# LWIR_FPGA_CSI.net
KiCad netlist of a schematic drawn in Altium Designer
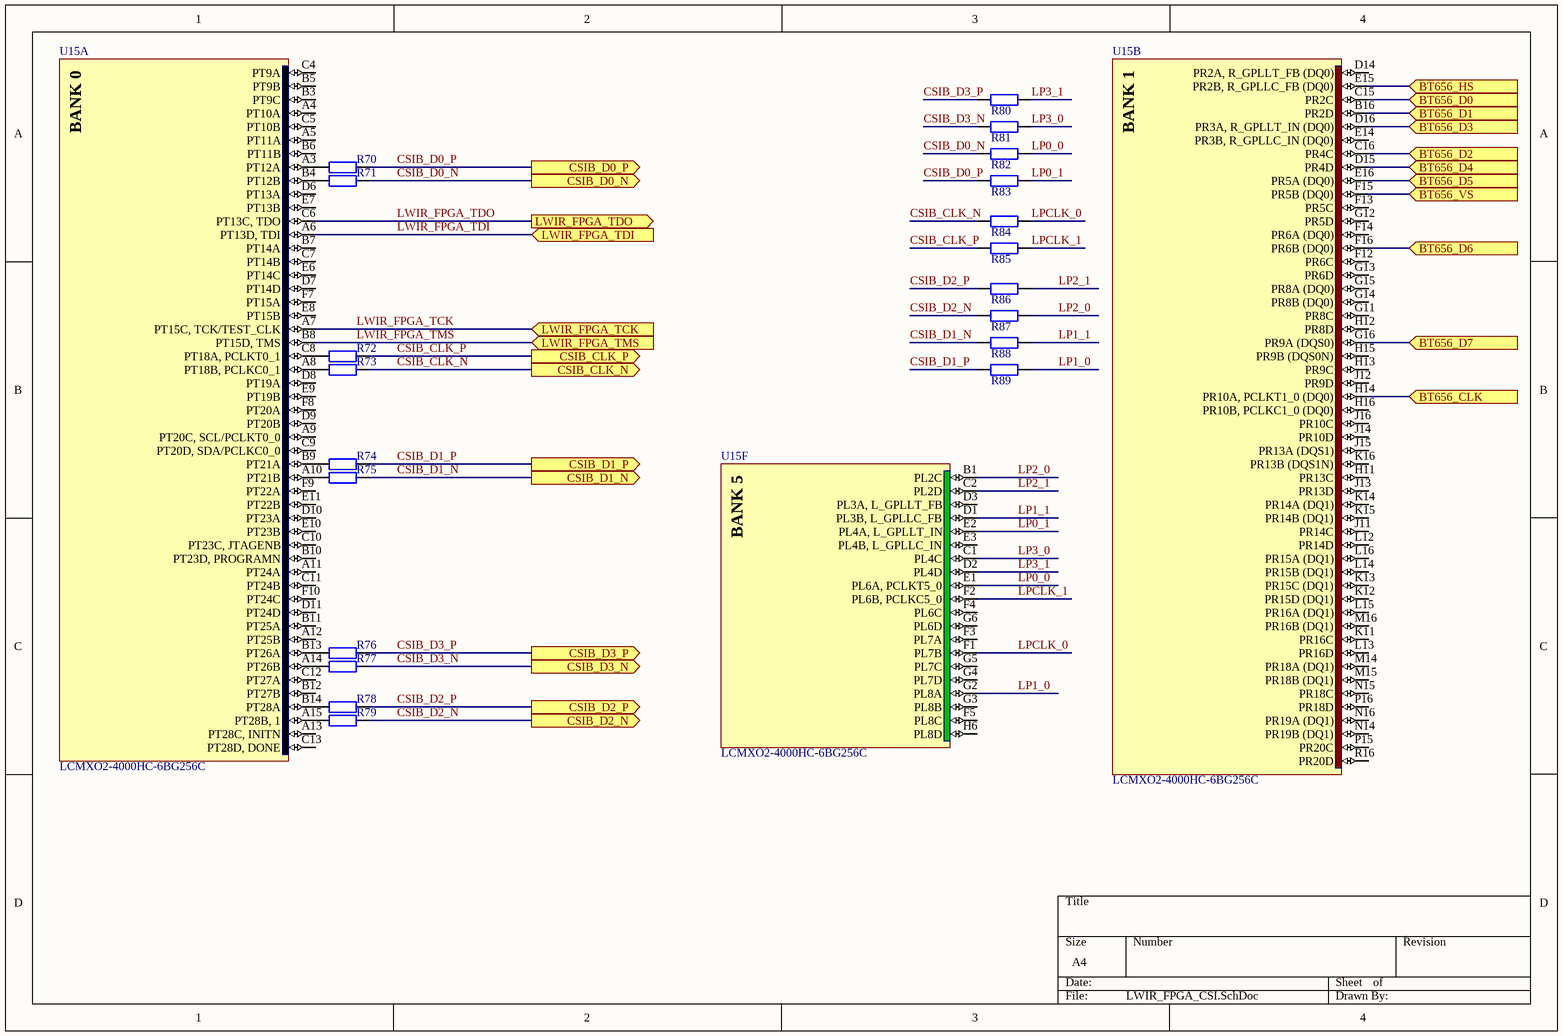
[diagram p0: LWIR_FPGA_CSI.SchDoc]

(export (version "E")
  (design (tool "Eeschema 10.0.6"))
  (components
    (comp (ref "R70")
      (value "CRCW0402330RFKED")
      (footprint "0402R_M")
      (description "RES SMD 330 OHM 1% 1/16W 0402")
      (fields (field (name "MANUFACTURER") "Vishay Dale") (field (name "TOLERANCE") "±1%"))
      (libsource (lib "KMTI-main") (part "CRCW0402330RFKED"))
    )
    (comp (ref "R71")
      (value "CRCW0402330RFKED")
      (footprint "0402R_M")
      (description "RES SMD 330 OHM 1% 1/16W 0402")
      (fields (field (name "MANUFACTURER") "Vishay Dale") (field (name "TOLERANCE") "±1%"))
      (libsource (lib "KMTI-main") (part "CRCW0402330RFKED"))
    )
    (comp (ref "R72")
      (value "CRCW0402330RFKED")
      (footprint "0402R_M")
      (description "RES SMD 330 OHM 1% 1/16W 0402")
      (fields (field (name "MANUFACTURER") "Vishay Dale") (field (name "TOLERANCE") "±1%"))
      (libsource (lib "KMTI-main") (part "CRCW0402330RFKED"))
    )
    (comp (ref "R73")
      (value "CRCW0402330RFKED")
      (footprint "0402R_M")
      (description "RES SMD 330 OHM 1% 1/16W 0402")
      (fields (field (name "MANUFACTURER") "Vishay Dale") (field (name "TOLERANCE") "±1%"))
      (libsource (lib "KMTI-main") (part "CRCW0402330RFKED"))
    )
    (comp (ref "R74")
      (value "CRCW0402330RFKED")
      (footprint "0402R_M")
      (description "RES SMD 330 OHM 1% 1/16W 0402")
      (fields (field (name "MANUFACTURER") "Vishay Dale") (field (name "TOLERANCE") "±1%"))
      (libsource (lib "KMTI-main") (part "CRCW0402330RFKED"))
    )
    (comp (ref "R75")
      (value "CRCW0402330RFKED")
      (footprint "0402R_M")
      (description "RES SMD 330 OHM 1% 1/16W 0402")
      (fields (field (name "MANUFACTURER") "Vishay Dale") (field (name "TOLERANCE") "±1%"))
      (libsource (lib "KMTI-main") (part "CRCW0402330RFKED"))
    )
    (comp (ref "R76")
      (value "CRCW0402330RFKED")
      (footprint "0402R_M")
      (description "RES SMD 330 OHM 1% 1/16W 0402")
      (fields (field (name "MANUFACTURER") "Vishay Dale") (field (name "TOLERANCE") "±1%"))
      (libsource (lib "KMTI-main") (part "CRCW0402330RFKED"))
    )
    (comp (ref "R77")
      (value "CRCW0402330RFKED")
      (footprint "0402R_M")
      (description "RES SMD 330 OHM 1% 1/16W 0402")
      (fields (field (name "MANUFACTURER") "Vishay Dale") (field (name "TOLERANCE") "±1%"))
      (libsource (lib "KMTI-main") (part "CRCW0402330RFKED"))
    )
    (comp (ref "R78")
      (value "CRCW0402330RFKED")
      (footprint "0402R_M")
      (description "RES SMD 330 OHM 1% 1/16W 0402")
      (fields (field (name "MANUFACTURER") "Vishay Dale") (field (name "TOLERANCE") "±1%"))
      (libsource (lib "KMTI-main") (part "CRCW0402330RFKED"))
    )
    (comp (ref "R79")
      (value "CRCW0402330RFKED")
      (footprint "0402R_M")
      (description "RES SMD 330 OHM 1% 1/16W 0402")
      (fields (field (name "MANUFACTURER") "Vishay Dale") (field (name "TOLERANCE") "±1%"))
      (libsource (lib "KMTI-main") (part "CRCW0402330RFKED"))
    )
    (comp (ref "R80")
      (value "CRCW040249R9FKED")
      (footprint "0402R_M")
      (description "RES SMD 49.9 OHM 1% 1/16W 0402")
      (fields (field (name "MANUFACTURER") "Vishay Dale") (field (name "TOLERANCE") "±1%"))
      (libsource (lib "KMTI-main") (part "CRCW040249R9FKED"))
    )
    (comp (ref "R81")
      (value "CRCW040249R9FKED")
      (footprint "0402R_M")
      (description "RES SMD 49.9 OHM 1% 1/16W 0402")
      (fields (field (name "MANUFACTURER") "Vishay Dale") (field (name "TOLERANCE") "±1%"))
      (libsource (lib "KMTI-main") (part "CRCW040249R9FKED"))
    )
    (comp (ref "R82")
      (value "CRCW040249R9FKED")
      (footprint "0402R_M")
      (description "RES SMD 49.9 OHM 1% 1/16W 0402")
      (fields (field (name "MANUFACTURER") "Vishay Dale") (field (name "TOLERANCE") "±1%"))
      (libsource (lib "KMTI-main") (part "CRCW040249R9FKED"))
    )
    (comp (ref "R83")
      (value "CRCW040249R9FKED")
      (footprint "0402R_M")
      (description "RES SMD 49.9 OHM 1% 1/16W 0402")
      (fields (field (name "MANUFACTURER") "Vishay Dale") (field (name "TOLERANCE") "±1%"))
      (libsource (lib "KMTI-main") (part "CRCW040249R9FKED"))
    )
    (comp (ref "R84")
      (value "CRCW040249R9FKED")
      (footprint "0402R_M")
      (description "RES SMD 49.9 OHM 1% 1/16W 0402")
      (fields (field (name "MANUFACTURER") "Vishay Dale") (field (name "TOLERANCE") "±1%"))
      (libsource (lib "KMTI-main") (part "CRCW040249R9FKED"))
    )
    (comp (ref "R85")
      (value "CRCW040249R9FKED")
      (footprint "0402R_M")
      (description "RES SMD 49.9 OHM 1% 1/16W 0402")
      (fields (field (name "MANUFACTURER") "Vishay Dale") (field (name "TOLERANCE") "±1%"))
      (libsource (lib "KMTI-main") (part "CRCW040249R9FKED"))
    )
    (comp (ref "R86")
      (value "CRCW040249R9FKED")
      (footprint "0402R_M")
      (description "RES SMD 49.9 OHM 1% 1/16W 0402")
      (fields (field (name "MANUFACTURER") "Vishay Dale") (field (name "TOLERANCE") "±1%"))
      (libsource (lib "") (part "CRCW040249R9FKED_1"))
    )
    (comp (ref "R87")
      (value "CRCW040249R9FKED")
      (footprint "0402R_M")
      (description "RES SMD 49.9 OHM 1% 1/16W 0402")
      (fields (field (name "MANUFACTURER") "Vishay Dale") (field (name "TOLERANCE") "±1%"))
      (libsource (lib "") (part "CRCW040249R9FKED_1"))
    )
    (comp (ref "R88")
      (value "CRCW040249R9FKED")
      (footprint "0402R_M")
      (description "RES SMD 49.9 OHM 1% 1/16W 0402")
      (fields (field (name "MANUFACTURER") "Vishay Dale") (field (name "TOLERANCE") "±1%"))
      (libsource (lib "") (part "CRCW040249R9FKED_1"))
    )
    (comp (ref "R89")
      (value "CRCW040249R9FKED")
      (footprint "0402R_M")
      (description "RES SMD 49.9 OHM 1% 1/16W 0402")
      (fields (field (name "MANUFACTURER") "Vishay Dale") (field (name "TOLERANCE") "±1%"))
      (libsource (lib "") (part "CRCW040249R9FKED_1"))
    )
    (comp (ref "U15")
      (value "LCMXO2-4000HC-6BG256C")
      (footprint "caBGA256")
      (libsource (lib "Altium Content Vault") (part "PLD-LTMXO2-4000-GA256"))
    )
  )
  (nets
    (net (code "1") (name "/BT656_CLK") (class "Default")
      (node (ref "U15") (pin "H14") (pinfunction "PR10A,_PCLKT1_0_(DQ0)_H14") (pintype "bidirectional"))
    )
    (net (code "2") (name "/BT656_D0") (class "Default")
      (node (ref "U15") (pin "C15") (pinfunction "PR2C_C15") (pintype "bidirectional"))
    )
    (net (code "3") (name "/BT656_D1") (class "Default")
      (node (ref "U15") (pin "B16") (pinfunction "PR2D_B16") (pintype "bidirectional"))
    )
    (net (code "4") (name "/BT656_D2") (class "Default")
      (node (ref "U15") (pin "C16") (pinfunction "PR4C_C16") (pintype "bidirectional"))
    )
    (net (code "5") (name "/BT656_D3") (class "Default")
      (node (ref "U15") (pin "D16") (pinfunction "PR3A,_R_GPLLT_IN_(DQ0)_D16") (pintype "bidirectional"))
    )
    (net (code "6") (name "/BT656_D4") (class "Default")
      (node (ref "U15") (pin "D15") (pinfunction "PR4D_D15") (pintype "bidirectional"))
    )
    (net (code "7") (name "/BT656_D5") (class "Default")
      (node (ref "U15") (pin "E16") (pinfunction "PR5A_(DQ0)_E16") (pintype "bidirectional"))
    )
    (net (code "8") (name "/BT656_D6") (class "Default")
      (node (ref "U15") (pin "F16") (pinfunction "PR6B_(DQ0)_F16") (pintype "bidirectional"))
    )
    (net (code "9") (name "/BT656_D7") (class "Default")
      (node (ref "U15") (pin "G16") (pinfunction "PR9A_(DQS0)_G16") (pintype "bidirectional"))
    )
    (net (code "10") (name "/BT656_HS") (class "Default")
      (node (ref "U15") (pin "E15") (pinfunction "PR2B,_R_GPLLC_FB_(DQ0)_E15") (pintype "bidirectional"))
    )
    (net (code "11") (name "/BT656_VS") (class "Default")
      (node (ref "U15") (pin "F15") (pinfunction "PR5B_(DQ0)_F15") (pintype "bidirectional"))
    )
    (net (code "12") (name "/CSIB_CLK_N") (class "Default")
      (node (ref "R73") (pin "2") (pinfunction "2_2") (pintype "passive"))
      (node (ref "R84") (pin "1") (pinfunction "1_1") (pintype "passive"))
    )
    (net (code "13") (name "/CSIB_CLK_P") (class "Default")
      (node (ref "R72") (pin "2") (pinfunction "2_2") (pintype "passive"))
      (node (ref "R85") (pin "1") (pinfunction "1_1") (pintype "passive"))
    )
    (net (code "14") (name "/CSIB_D0_N") (class "Default")
      (node (ref "R71") (pin "2") (pinfunction "2_2") (pintype "passive"))
      (node (ref "R82") (pin "1") (pinfunction "1_1") (pintype "passive"))
    )
    (net (code "15") (name "/CSIB_D0_P") (class "Default")
      (node (ref "R70") (pin "2") (pinfunction "2_2") (pintype "passive"))
      (node (ref "R83") (pin "1") (pinfunction "1_1") (pintype "passive"))
    )
    (net (code "16") (name "/CSIB_D1_N") (class "Default")
      (node (ref "R75") (pin "2") (pinfunction "2_2") (pintype "passive"))
      (node (ref "R88") (pin "2") (pinfunction "2_2") (pintype "passive"))
    )
    (net (code "17") (name "/CSIB_D1_P") (class "Default")
      (node (ref "R74") (pin "2") (pinfunction "2_2") (pintype "passive"))
      (node (ref "R89") (pin "2") (pinfunction "2_2") (pintype "passive"))
    )
    (net (code "18") (name "/CSIB_D2_N") (class "Default")
      (node (ref "R79") (pin "2") (pinfunction "2_2") (pintype "passive"))
      (node (ref "R87") (pin "2") (pinfunction "2_2") (pintype "passive"))
    )
    (net (code "19") (name "/CSIB_D2_P") (class "Default")
      (node (ref "R78") (pin "2") (pinfunction "2_2") (pintype "passive"))
      (node (ref "R86") (pin "2") (pinfunction "2_2") (pintype "passive"))
    )
    (net (code "20") (name "/CSIB_D3_N") (class "Default")
      (node (ref "R77") (pin "2") (pinfunction "2_2") (pintype "passive"))
      (node (ref "R81") (pin "1") (pinfunction "1_1") (pintype "passive"))
    )
    (net (code "21") (name "/CSIB_D3_P") (class "Default")
      (node (ref "R76") (pin "2") (pinfunction "2_2") (pintype "passive"))
      (node (ref "R80") (pin "1") (pinfunction "1_1") (pintype "passive"))
    )
    (net (code "22") (name "/LP0_0") (class "Default")
      (node (ref "R82") (pin "2") (pinfunction "2_2") (pintype "passive"))
      (node (ref "U15") (pin "E1") (pinfunction "PL6A,_PCLKT5_0_E1") (pintype "bidirectional"))
    )
    (net (code "23") (name "/LP0_1") (class "Default")
      (node (ref "R83") (pin "2") (pinfunction "2_2") (pintype "passive"))
      (node (ref "U15") (pin "E2") (pinfunction "PL4A,_L_GPLLT_IN_E2") (pintype "bidirectional"))
    )
    (net (code "24") (name "/LP1_0") (class "Default")
      (node (ref "R89") (pin "1") (pinfunction "1_1") (pintype "passive"))
      (node (ref "U15") (pin "G2") (pinfunction "PL8A_G2") (pintype "bidirectional"))
    )
    (net (code "25") (name "/LP1_1") (class "Default")
      (node (ref "R88") (pin "1") (pinfunction "1_1") (pintype "passive"))
      (node (ref "U15") (pin "D1") (pinfunction "PL3B,_L_GPLLC_FB_D1") (pintype "bidirectional"))
    )
    (net (code "26") (name "/LP2_0") (class "Default")
      (node (ref "R87") (pin "1") (pinfunction "1_1") (pintype "passive"))
      (node (ref "U15") (pin "B1") (pinfunction "PL2C_B1") (pintype "bidirectional"))
    )
    (net (code "27") (name "/LP2_1") (class "Default")
      (node (ref "R86") (pin "1") (pinfunction "1_1") (pintype "passive"))
      (node (ref "U15") (pin "C2") (pinfunction "PL2D_C2") (pintype "bidirectional"))
    )
    (net (code "28") (name "/LP3_0") (class "Default")
      (node (ref "R81") (pin "2") (pinfunction "2_2") (pintype "passive"))
      (node (ref "U15") (pin "C1") (pinfunction "PL4C_C1") (pintype "bidirectional"))
    )
    (net (code "29") (name "/LP3_1") (class "Default")
      (node (ref "R80") (pin "2") (pinfunction "2_2") (pintype "passive"))
      (node (ref "U15") (pin "D2") (pinfunction "PL4D_D2") (pintype "bidirectional"))
    )
    (net (code "30") (name "/LPCLK_0") (class "Default")
      (node (ref "R84") (pin "2") (pinfunction "2_2") (pintype "passive"))
      (node (ref "U15") (pin "F1") (pinfunction "PL7B_F1") (pintype "bidirectional"))
    )
    (net (code "31") (name "/LPCLK_1") (class "Default")
      (node (ref "R85") (pin "2") (pinfunction "2_2") (pintype "passive"))
      (node (ref "U15") (pin "F2") (pinfunction "PL6B,_PCLKC5_0_F2") (pintype "bidirectional"))
    )
    (net (code "32") (name "/LWIR_FPGA_TCK") (class "Default")
      (node (ref "U15") (pin "A7") (pinfunction "PT15C,_TCK/TEST_CLK_A7") (pintype "bidirectional"))
    )
    (net (code "33") (name "/LWIR_FPGA_TDI") (class "Default")
      (node (ref "U15") (pin "A6") (pinfunction "PT13D,_TDI_A6") (pintype "bidirectional"))
    )
    (net (code "34") (name "/LWIR_FPGA_TDO") (class "Default")
      (node (ref "U15") (pin "C6") (pinfunction "PT13C,_TDO_C6") (pintype "bidirectional"))
    )
    (net (code "35") (name "/LWIR_FPGA_TMS") (class "Default")
      (node (ref "U15") (pin "B8") (pinfunction "PT15D,_TMS_B8") (pintype "bidirectional"))
    )
    (net (code "36") (name "Net-(U15A-PT12A)") (class "Default")
      (node (ref "R70") (pin "1") (pinfunction "1_1") (pintype "passive"))
      (node (ref "U15") (pin "A3") (pinfunction "PT12A_A3") (pintype "bidirectional"))
    )
    (net (code "37") (name "Net-(U15A-PT12B)") (class "Default")
      (node (ref "R71") (pin "1") (pinfunction "1_1") (pintype "passive"))
      (node (ref "U15") (pin "B4") (pinfunction "PT12B_B4") (pintype "bidirectional"))
    )
    (net (code "38") (name "Net-(U15A-PT18A,_PCLKT0_1)") (class "Default")
      (node (ref "R72") (pin "1") (pinfunction "1_1") (pintype "passive"))
      (node (ref "U15") (pin "C8") (pinfunction "PT18A,_PCLKT0_1_C8") (pintype "bidirectional"))
    )
    (net (code "39") (name "Net-(U15A-PT18B,_PCLKC0_1)") (class "Default")
      (node (ref "R73") (pin "1") (pinfunction "1_1") (pintype "passive"))
      (node (ref "U15") (pin "A8") (pinfunction "PT18B,_PCLKC0_1_A8") (pintype "bidirectional"))
    )
    (net (code "40") (name "Net-(U15A-PT21A)") (class "Default")
      (node (ref "R74") (pin "1") (pinfunction "1_1") (pintype "passive"))
      (node (ref "U15") (pin "B9") (pinfunction "PT21A_B9") (pintype "bidirectional"))
    )
    (net (code "41") (name "Net-(U15A-PT21B)") (class "Default")
      (node (ref "R75") (pin "1") (pinfunction "1_1") (pintype "passive"))
      (node (ref "U15") (pin "A10") (pinfunction "PT21B_A10") (pintype "bidirectional"))
    )
    (net (code "42") (name "Net-(U15A-PT26A)") (class "Default")
      (node (ref "R76") (pin "1") (pinfunction "1_1") (pintype "passive"))
      (node (ref "U15") (pin "B13") (pinfunction "PT26A_B13") (pintype "bidirectional"))
    )
    (net (code "43") (name "Net-(U15A-PT26B)") (class "Default")
      (node (ref "R77") (pin "1") (pinfunction "1_1") (pintype "passive"))
      (node (ref "U15") (pin "A14") (pinfunction "PT26B_A14") (pintype "bidirectional"))
    )
    (net (code "44") (name "Net-(U15A-PT28A)") (class "Default")
      (node (ref "R78") (pin "1") (pinfunction "1_1") (pintype "passive"))
      (node (ref "U15") (pin "B14") (pinfunction "PT28A_B14") (pintype "bidirectional"))
    )
    (net (code "45") (name "Net-(U15A-PT28B,_1)") (class "Default")
      (node (ref "R79") (pin "1") (pinfunction "1_1") (pintype "passive"))
      (node (ref "U15") (pin "A15") (pinfunction "PT28B,_1_A15") (pintype "bidirectional"))
    )
    (net (code "46") (name "unconnected-(U15A-PT9A-PadC4)") (class "Default")
      (node (ref "U15") (pin "C4") (pinfunction "PT9A_C4") (pintype "bidirectional"))
    )
    (net (code "47") (name "unconnected-(U15A-PT9B-PadB5)") (class "Default")
      (node (ref "U15") (pin "B5") (pinfunction "PT9B_B5") (pintype "bidirectional"))
    )
    (net (code "48") (name "unconnected-(U15A-PT9C-PadB3)") (class "Default")
      (node (ref "U15") (pin "B3") (pinfunction "PT9C_B3") (pintype "bidirectional"))
    )
    (net (code "49") (name "unconnected-(U15A-PT10A-PadA4)") (class "Default")
      (node (ref "U15") (pin "A4") (pinfunction "PT10A_A4") (pintype "bidirectional"))
    )
    (net (code "50") (name "unconnected-(U15A-PT10B-PadC5)") (class "Default")
      (node (ref "U15") (pin "C5") (pinfunction "PT10B_C5") (pintype "bidirectional"))
    )
    (net (code "51") (name "unconnected-(U15A-PT11A-PadA5)") (class "Default")
      (node (ref "U15") (pin "A5") (pinfunction "PT11A_A5") (pintype "bidirectional"))
    )
    (net (code "52") (name "unconnected-(U15A-PT11B-PadB6)") (class "Default")
      (node (ref "U15") (pin "B6") (pinfunction "PT11B_B6") (pintype "bidirectional"))
    )
    (net (code "53") (name "unconnected-(U15A-PT13A-PadD6)") (class "Default")
      (node (ref "U15") (pin "D6") (pinfunction "PT13A_D6") (pintype "bidirectional"))
    )
    (net (code "54") (name "unconnected-(U15A-PT13B-PadE7)") (class "Default")
      (node (ref "U15") (pin "E7") (pinfunction "PT13B_E7") (pintype "bidirectional"))
    )
    (net (code "55") (name "unconnected-(U15A-PT14A-PadB7)") (class "Default")
      (node (ref "U15") (pin "B7") (pinfunction "PT14A_B7") (pintype "bidirectional"))
    )
    (net (code "56") (name "unconnected-(U15A-PT14B-PadC7)") (class "Default")
      (node (ref "U15") (pin "C7") (pinfunction "PT14B_C7") (pintype "bidirectional"))
    )
    (net (code "57") (name "unconnected-(U15A-PT14C-PadE6)") (class "Default")
      (node (ref "U15") (pin "E6") (pinfunction "PT14C_E6") (pintype "bidirectional"))
    )
    (net (code "58") (name "unconnected-(U15A-PT14D-PadD7)") (class "Default")
      (node (ref "U15") (pin "D7") (pinfunction "PT14D_D7") (pintype "bidirectional"))
    )
    (net (code "59") (name "unconnected-(U15A-PT15A-PadF7)") (class "Default")
      (node (ref "U15") (pin "F7") (pinfunction "PT15A_F7") (pintype "bidirectional"))
    )
    (net (code "60") (name "unconnected-(U15A-PT15B-PadE8)") (class "Default")
      (node (ref "U15") (pin "E8") (pinfunction "PT15B_E8") (pintype "bidirectional"))
    )
    (net (code "61") (name "unconnected-(U15A-PT19A-PadD8)") (class "Default")
      (node (ref "U15") (pin "D8") (pinfunction "PT19A_D8") (pintype "bidirectional"))
    )
    (net (code "62") (name "unconnected-(U15A-PT19B-PadE9)") (class "Default")
      (node (ref "U15") (pin "E9") (pinfunction "PT19B_E9") (pintype "bidirectional"))
    )
    (net (code "63") (name "unconnected-(U15A-PT20A-PadF8)") (class "Default")
      (node (ref "U15") (pin "F8") (pinfunction "PT20A_F8") (pintype "bidirectional"))
    )
    (net (code "64") (name "unconnected-(U15A-PT20B-PadD9)") (class "Default")
      (node (ref "U15") (pin "D9") (pinfunction "PT20B_D9") (pintype "bidirectional"))
    )
    (net (code "65") (name "unconnected-(U15A-PT20C,_SCL{slash}PCLKT0_0-PadA9)") (class "Default")
      (node (ref "U15") (pin "A9") (pinfunction "PT20C,_SCL/PCLKT0_0_A9") (pintype "bidirectional"))
    )
    (net (code "66") (name "unconnected-(U15A-PT20D,_SDA{slash}PCLKC0_0-PadC9)") (class "Default")
      (node (ref "U15") (pin "C9") (pinfunction "PT20D,_SDA/PCLKC0_0_C9") (pintype "bidirectional"))
    )
    (net (code "67") (name "unconnected-(U15A-PT22A-PadF9)") (class "Default")
      (node (ref "U15") (pin "F9") (pinfunction "PT22A_F9") (pintype "bidirectional"))
    )
    (net (code "68") (name "unconnected-(U15A-PT22B-PadE11)") (class "Default")
      (node (ref "U15") (pin "E11") (pinfunction "PT22B_E11") (pintype "bidirectional"))
    )
    (net (code "69") (name "unconnected-(U15A-PT23A-PadD10)") (class "Default")
      (node (ref "U15") (pin "D10") (pinfunction "PT23A_D10") (pintype "bidirectional"))
    )
    (net (code "70") (name "unconnected-(U15A-PT23B-PadE10)") (class "Default")
      (node (ref "U15") (pin "E10") (pinfunction "PT23B_E10") (pintype "bidirectional"))
    )
    (net (code "71") (name "unconnected-(U15A-PT23C,_JTAGENB-PadC10)") (class "Default")
      (node (ref "U15") (pin "C10") (pinfunction "PT23C,_JTAGENB_C10") (pintype "bidirectional"))
    )
    (net (code "72") (name "unconnected-(U15A-PT23D,_PROGRAMN-PadB10)") (class "Default")
      (node (ref "U15") (pin "B10") (pinfunction "PT23D,_PROGRAMN_B10") (pintype "bidirectional"))
    )
    (net (code "73") (name "unconnected-(U15A-PT24A-PadA11)") (class "Default")
      (node (ref "U15") (pin "A11") (pinfunction "PT24A_A11") (pintype "bidirectional"))
    )
    (net (code "74") (name "unconnected-(U15A-PT24B-PadC11)") (class "Default")
      (node (ref "U15") (pin "C11") (pinfunction "PT24B_C11") (pintype "bidirectional"))
    )
    (net (code "75") (name "unconnected-(U15A-PT24C-PadF10)") (class "Default")
      (node (ref "U15") (pin "F10") (pinfunction "PT24C_F10") (pintype "bidirectional"))
    )
    (net (code "76") (name "unconnected-(U15A-PT24D-PadD11)") (class "Default")
      (node (ref "U15") (pin "D11") (pinfunction "PT24D_D11") (pintype "bidirectional"))
    )
    (net (code "77") (name "unconnected-(U15A-PT25A-PadB11)") (class "Default")
      (node (ref "U15") (pin "B11") (pinfunction "PT25A_B11") (pintype "bidirectional"))
    )
    (net (code "78") (name "unconnected-(U15A-PT25B-PadA12)") (class "Default")
      (node (ref "U15") (pin "A12") (pinfunction "PT25B_A12") (pintype "bidirectional"))
    )
    (net (code "79") (name "unconnected-(U15A-PT27A-PadC12)") (class "Default")
      (node (ref "U15") (pin "C12") (pinfunction "PT27A_C12") (pintype "bidirectional"))
    )
    (net (code "80") (name "unconnected-(U15A-PT27B-PadB12)") (class "Default")
      (node (ref "U15") (pin "B12") (pinfunction "PT27B_B12") (pintype "bidirectional"))
    )
    (net (code "81") (name "unconnected-(U15A-PT28C,_INITN-PadA13)") (class "Default")
      (node (ref "U15") (pin "A13") (pinfunction "PT28C,_INITN_A13") (pintype "bidirectional"))
    )
    (net (code "82") (name "unconnected-(U15A-PT28D,_DONE-PadC13)") (class "Default")
      (node (ref "U15") (pin "C13") (pinfunction "PT28D,_DONE_C13") (pintype "bidirectional"))
    )
    (net (code "83") (name "unconnected-(U15B-PR2A,_R_GPLLT_FB_(DQ0)-PadD14)") (class "Default")
      (node (ref "U15") (pin "D14") (pinfunction "PR2A,_R_GPLLT_FB_(DQ0)_D14") (pintype "bidirectional"))
    )
    (net (code "84") (name "unconnected-(U15B-PR3B,_R_GPLLC_IN_(DQ0)-PadE14)") (class "Default")
      (node (ref "U15") (pin "E14") (pinfunction "PR3B,_R_GPLLC_IN_(DQ0)_E14") (pintype "bidirectional"))
    )
    (net (code "85") (name "unconnected-(U15B-PR5C-PadF13)") (class "Default")
      (node (ref "U15") (pin "F13") (pinfunction "PR5C_F13") (pintype "bidirectional"))
    )
    (net (code "86") (name "unconnected-(U15B-PR5D-PadG12)") (class "Default")
      (node (ref "U15") (pin "G12") (pinfunction "PR5D_G12") (pintype "bidirectional"))
    )
    (net (code "87") (name "unconnected-(U15B-PR6A_(DQ0)-PadF14)") (class "Default")
      (node (ref "U15") (pin "F14") (pinfunction "PR6A_(DQ0)_F14") (pintype "bidirectional"))
    )
    (net (code "88") (name "unconnected-(U15B-PR6C-PadF12)") (class "Default")
      (node (ref "U15") (pin "F12") (pinfunction "PR6C_F12") (pintype "bidirectional"))
    )
    (net (code "89") (name "unconnected-(U15B-PR6D-PadG13)") (class "Default")
      (node (ref "U15") (pin "G13") (pinfunction "PR6D_G13") (pintype "bidirectional"))
    )
    (net (code "90") (name "unconnected-(U15B-PR8A_(DQ0)-PadG15)") (class "Default")
      (node (ref "U15") (pin "G15") (pinfunction "PR8A_(DQ0)_G15") (pintype "bidirectional"))
    )
    (net (code "91") (name "unconnected-(U15B-PR8B_(DQ0)-PadG14)") (class "Default")
      (node (ref "U15") (pin "G14") (pinfunction "PR8B_(DQ0)_G14") (pintype "bidirectional"))
    )
    (net (code "92") (name "unconnected-(U15B-PR8C-PadG11)") (class "Default")
      (node (ref "U15") (pin "G11") (pinfunction "PR8C_G11") (pintype "bidirectional"))
    )
    (net (code "93") (name "unconnected-(U15B-PR8D-PadH12)") (class "Default")
      (node (ref "U15") (pin "H12") (pinfunction "PR8D_H12") (pintype "bidirectional"))
    )
    (net (code "94") (name "unconnected-(U15B-PR9B_(DQS0N)-PadH15)") (class "Default")
      (node (ref "U15") (pin "H15") (pinfunction "PR9B_(DQS0N)_H15") (pintype "bidirectional"))
    )
    (net (code "95") (name "unconnected-(U15B-PR9C-PadH13)") (class "Default")
      (node (ref "U15") (pin "H13") (pinfunction "PR9C_H13") (pintype "bidirectional"))
    )
    (net (code "96") (name "unconnected-(U15B-PR9D-PadJ12)") (class "Default")
      (node (ref "U15") (pin "J12") (pinfunction "PR9D_J12") (pintype "bidirectional"))
    )
    (net (code "97") (name "unconnected-(U15B-PR10B,_PCLKC1_0_(DQ0)-PadH16)") (class "Default")
      (node (ref "U15") (pin "H16") (pinfunction "PR10B,_PCLKC1_0_(DQ0)_H16") (pintype "bidirectional"))
    )
    (net (code "98") (name "unconnected-(U15B-PR10C-PadJ16)") (class "Default")
      (node (ref "U15") (pin "J16") (pinfunction "PR10C_J16") (pintype "bidirectional"))
    )
    (net (code "99") (name "unconnected-(U15B-PR10D-PadJ14)") (class "Default")
      (node (ref "U15") (pin "J14") (pinfunction "PR10D_J14") (pintype "bidirectional"))
    )
    (net (code "100") (name "unconnected-(U15B-PR13A_(DQS1)-PadJ15)") (class "Default")
      (node (ref "U15") (pin "J15") (pinfunction "PR13A_(DQS1)_J15") (pintype "bidirectional"))
    )
    (net (code "101") (name "unconnected-(U15B-PR13B_(DQS1N)-PadK16)") (class "Default")
      (node (ref "U15") (pin "K16") (pinfunction "PR13B_(DQS1N)_K16") (pintype "bidirectional"))
    )
    (net (code "102") (name "unconnected-(U15B-PR13C-PadH11)") (class "Default")
      (node (ref "U15") (pin "H11") (pinfunction "PR13C_H11") (pintype "bidirectional"))
    )
    (net (code "103") (name "unconnected-(U15B-PR13D-PadJ13)") (class "Default")
      (node (ref "U15") (pin "J13") (pinfunction "PR13D_J13") (pintype "bidirectional"))
    )
    (net (code "104") (name "unconnected-(U15B-PR14A_(DQ1)-PadK14)") (class "Default")
      (node (ref "U15") (pin "K14") (pinfunction "PR14A_(DQ1)_K14") (pintype "bidirectional"))
    )
    (net (code "105") (name "unconnected-(U15B-PR14B_(DQ1)-PadK15)") (class "Default")
      (node (ref "U15") (pin "K15") (pinfunction "PR14B_(DQ1)_K15") (pintype "bidirectional"))
    )
    (net (code "106") (name "unconnected-(U15B-PR14C-PadJ11)") (class "Default")
      (node (ref "U15") (pin "J11") (pinfunction "PR14C_J11") (pintype "bidirectional"))
    )
    (net (code "107") (name "unconnected-(U15B-PR14D-PadL12)") (class "Default")
      (node (ref "U15") (pin "L12") (pinfunction "PR14D_L12") (pintype "bidirectional"))
    )
    (net (code "108") (name "unconnected-(U15B-PR15A_(DQ1)-PadL16)") (class "Default")
      (node (ref "U15") (pin "L16") (pinfunction "PR15A_(DQ1)_L16") (pintype "bidirectional"))
    )
    (net (code "109") (name "unconnected-(U15B-PR15B_(DQ1)-PadL14)") (class "Default")
      (node (ref "U15") (pin "L14") (pinfunction "PR15B_(DQ1)_L14") (pintype "bidirectional"))
    )
    (net (code "110") (name "unconnected-(U15B-PR15C_(DQ1)-PadK13)") (class "Default")
      (node (ref "U15") (pin "K13") (pinfunction "PR15C_(DQ1)_K13") (pintype "bidirectional"))
    )
    (net (code "111") (name "unconnected-(U15B-PR15D_(DQ1)-PadK12)") (class "Default")
      (node (ref "U15") (pin "K12") (pinfunction "PR15D_(DQ1)_K12") (pintype "bidirectional"))
    )
    (net (code "112") (name "unconnected-(U15B-PR16A_(DQ1)-PadL15)") (class "Default")
      (node (ref "U15") (pin "L15") (pinfunction "PR16A_(DQ1)_L15") (pintype "bidirectional"))
    )
    (net (code "113") (name "unconnected-(U15B-PR16B_(DQ1)-PadM16)") (class "Default")
      (node (ref "U15") (pin "M16") (pinfunction "PR16B_(DQ1)_M16") (pintype "bidirectional"))
    )
    (net (code "114") (name "unconnected-(U15B-PR16C-PadK11)") (class "Default")
      (node (ref "U15") (pin "K11") (pinfunction "PR16C_K11") (pintype "bidirectional"))
    )
    (net (code "115") (name "unconnected-(U15B-PR16D-PadL13)") (class "Default")
      (node (ref "U15") (pin "L13") (pinfunction "PR16D_L13") (pintype "bidirectional"))
    )
    (net (code "116") (name "unconnected-(U15B-PR18A_(DQ1)-PadM14)") (class "Default")
      (node (ref "U15") (pin "M14") (pinfunction "PR18A_(DQ1)_M14") (pintype "bidirectional"))
    )
    (net (code "117") (name "unconnected-(U15B-PR18B_(DQ1)-PadM15)") (class "Default")
      (node (ref "U15") (pin "M15") (pinfunction "PR18B_(DQ1)_M15") (pintype "bidirectional"))
    )
    (net (code "118") (name "unconnected-(U15B-PR18C-PadN15)") (class "Default")
      (node (ref "U15") (pin "N15") (pinfunction "PR18C_N15") (pintype "bidirectional"))
    )
    (net (code "119") (name "unconnected-(U15B-PR18D-PadP16)") (class "Default")
      (node (ref "U15") (pin "P16") (pinfunction "PR18D_P16") (pintype "bidirectional"))
    )
    (net (code "120") (name "unconnected-(U15B-PR19A_(DQ1)-PadN16)") (class "Default")
      (node (ref "U15") (pin "N16") (pinfunction "PR19A_(DQ1)_N16") (pintype "bidirectional"))
    )
    (net (code "121") (name "unconnected-(U15B-PR19B_(DQ1)-PadN14)") (class "Default")
      (node (ref "U15") (pin "N14") (pinfunction "PR19B_(DQ1)_N14") (pintype "bidirectional"))
    )
    (net (code "122") (name "unconnected-(U15B-PR20C-PadP15)") (class "Default")
      (node (ref "U15") (pin "P15") (pinfunction "PR20C_P15") (pintype "bidirectional"))
    )
    (net (code "123") (name "unconnected-(U15B-PR20D-PadR16)") (class "Default")
      (node (ref "U15") (pin "R16") (pinfunction "PR20D_R16") (pintype "bidirectional"))
    )
    (net (code "124") (name "unconnected-(U15F-PL3A,_L_GPLLT_FB-PadD3)") (class "Default")
      (node (ref "U15") (pin "D3") (pinfunction "PL3A,_L_GPLLT_FB_D3") (pintype "bidirectional"))
    )
    (net (code "125") (name "unconnected-(U15F-PL4B,_L_GPLLC_IN-PadE3)") (class "Default")
      (node (ref "U15") (pin "E3") (pinfunction "PL4B,_L_GPLLC_IN_E3") (pintype "bidirectional"))
    )
    (net (code "126") (name "unconnected-(U15F-PL6C-PadF4)") (class "Default")
      (node (ref "U15") (pin "F4") (pinfunction "PL6C_F4") (pintype "bidirectional"))
    )
    (net (code "127") (name "unconnected-(U15F-PL6D-PadG6)") (class "Default")
      (node (ref "U15") (pin "G6") (pinfunction "PL6D_G6") (pintype "bidirectional"))
    )
    (net (code "128") (name "unconnected-(U15F-PL7A-PadF3)") (class "Default")
      (node (ref "U15") (pin "F3") (pinfunction "PL7A_F3") (pintype "bidirectional"))
    )
    (net (code "129") (name "unconnected-(U15F-PL7C-PadG5)") (class "Default")
      (node (ref "U15") (pin "G5") (pinfunction "PL7C_G5") (pintype "bidirectional"))
    )
    (net (code "130") (name "unconnected-(U15F-PL7D-PadG4)") (class "Default")
      (node (ref "U15") (pin "G4") (pinfunction "PL7D_G4") (pintype "bidirectional"))
    )
    (net (code "131") (name "unconnected-(U15F-PL8B-PadG3)") (class "Default")
      (node (ref "U15") (pin "G3") (pinfunction "PL8B_G3") (pintype "bidirectional"))
    )
    (net (code "132") (name "unconnected-(U15F-PL8C-PadF5)") (class "Default")
      (node (ref "U15") (pin "F5") (pinfunction "PL8C_F5") (pintype "bidirectional"))
    )
    (net (code "133") (name "unconnected-(U15F-PL8D-PadH6)") (class "Default")
      (node (ref "U15") (pin "H6") (pinfunction "PL8D_H6") (pintype "bidirectional"))
    )
  )
)
